# 4ch_mosfet_switch.net
KiCad netlist of a schematic drawn in EAGLE
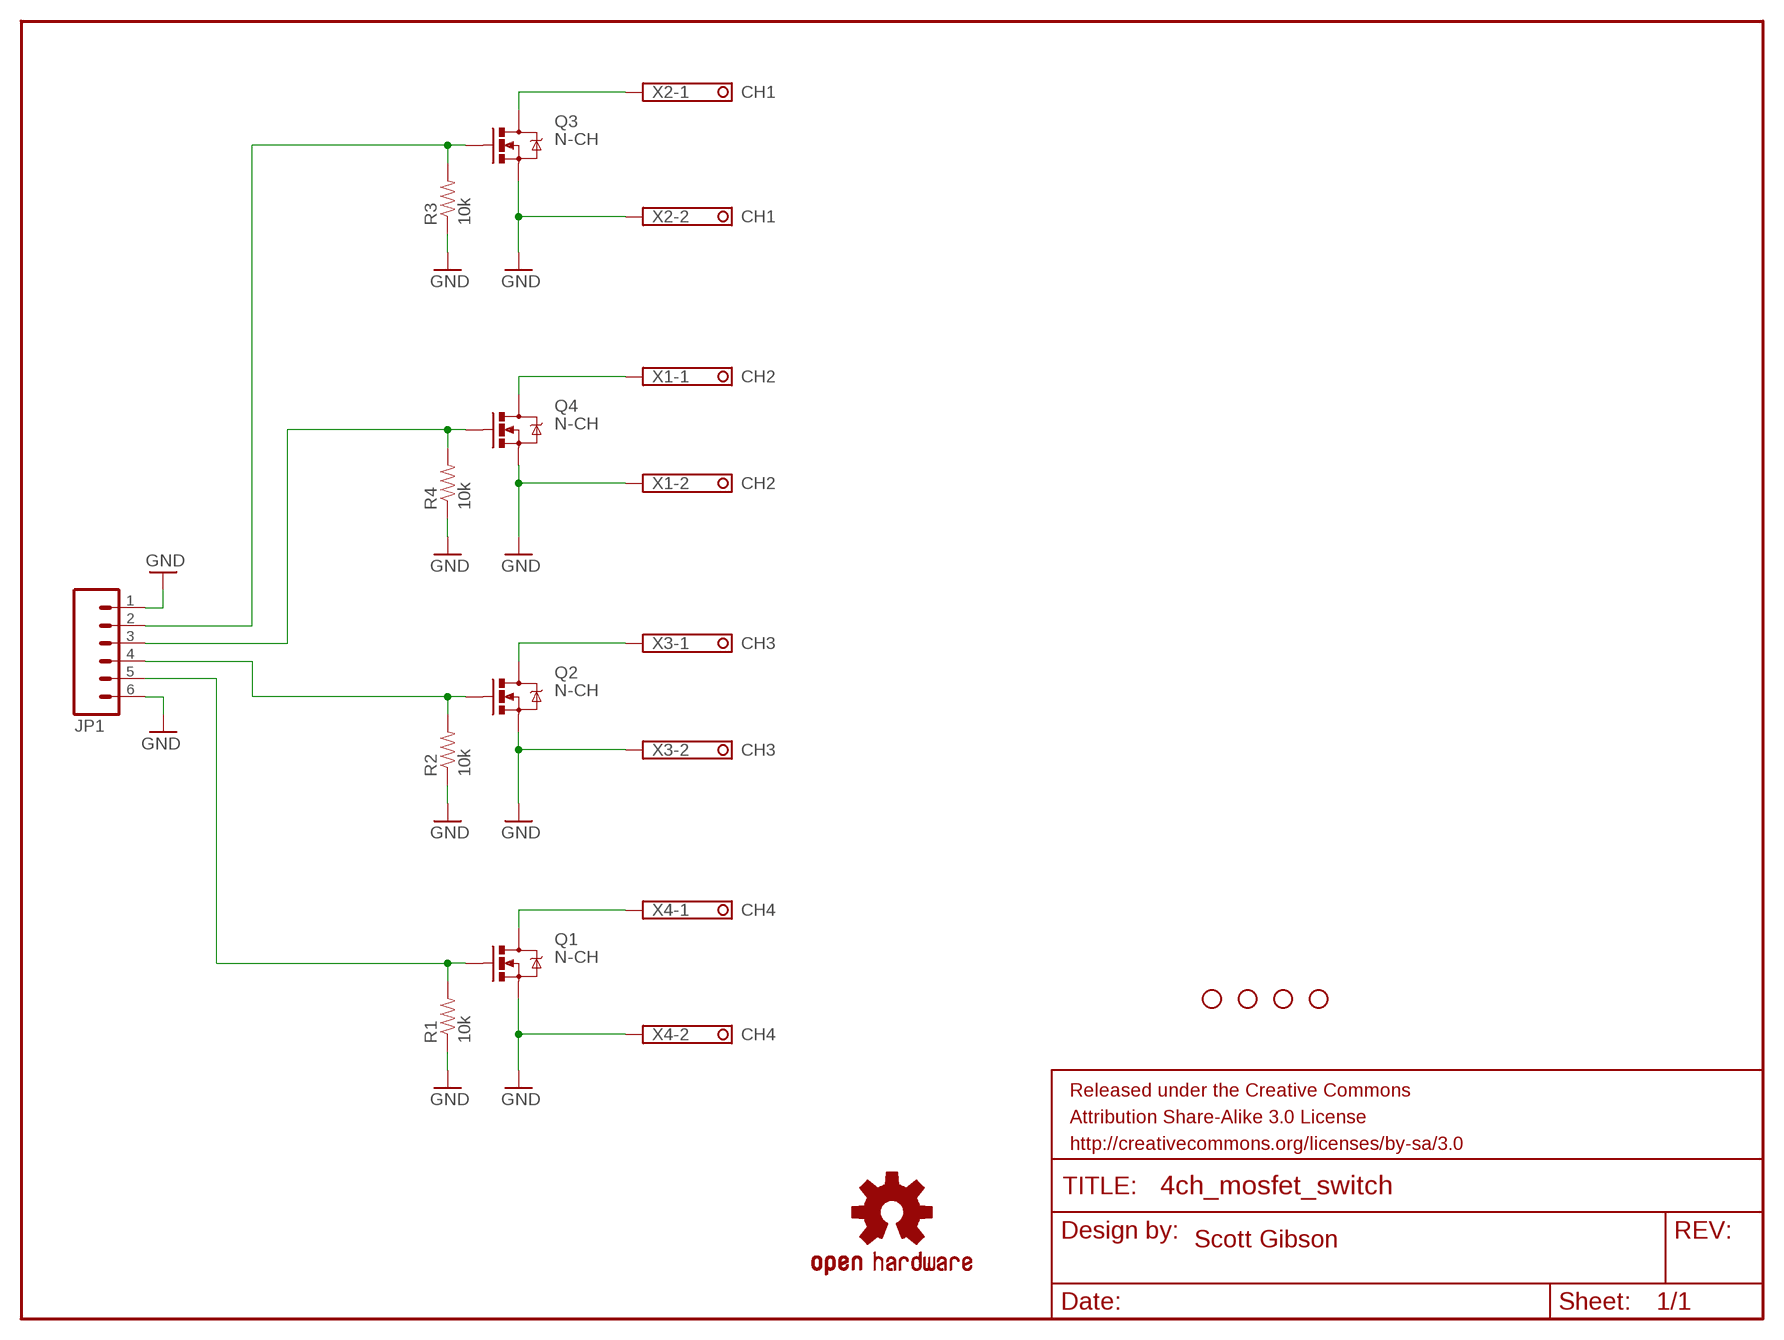
[diagram p0: schematic, sheet 1]

(export (version "E")
  (design (tool "Eeschema 10.0.6"))
  (components
    (comp (ref "FRAME1")
      (value "FRAME-LETTER")
      (footprint "eagle-import:CREATIVE_COMMONS")
      (libsource (lib "eagle-import") (part "FRAME-LETTER"))
    )
    (comp (ref "JP1")
      (value "M06LOCK_LONGPADS")
      (footprint "eagle-import:1X06_LOCK_LONGPADS")
      (libsource (lib "eagle-import") (part "M06LOCK_LONGPADS"))
    )
    (comp (ref "LOGO1")
      (value "OSHW-LOGOM")
      (footprint "eagle-import:OSHW-LOGO-M")
      (libsource (lib "eagle-import") (part "OSHW-LOGOM"))
    )
    (comp (ref "Q1")
      (value "N-CH")
      (footprint "eagle-import:TO220V")
      (libsource (lib "eagle-import") (part "MOSFET-NCHANNELFQP30N06L"))
    )
    (comp (ref "Q2")
      (value "N-CH")
      (footprint "eagle-import:TO220V")
      (libsource (lib "eagle-import") (part "MOSFET-NCHANNELFQP30N06L"))
    )
    (comp (ref "Q3")
      (value "N-CH")
      (footprint "eagle-import:TO220V")
      (libsource (lib "eagle-import") (part "MOSFET-NCHANNELFQP30N06L"))
    )
    (comp (ref "Q4")
      (value "N-CH")
      (footprint "eagle-import:TO220V")
      (libsource (lib "eagle-import") (part "MOSFET-NCHANNELFQP30N06L"))
    )
    (comp (ref "R1")
      (value "10k")
      (footprint "eagle-import:AXIAL-0.3")
      (libsource (lib "eagle-import") (part "RESISTORAXIAL-0.3"))
    )
    (comp (ref "R2")
      (value "10k")
      (footprint "eagle-import:AXIAL-0.3")
      (libsource (lib "eagle-import") (part "RESISTORAXIAL-0.3"))
    )
    (comp (ref "R3")
      (value "10k")
      (footprint "eagle-import:AXIAL-0.3")
      (libsource (lib "eagle-import") (part "RESISTORAXIAL-0.3"))
    )
    (comp (ref "R4")
      (value "10k")
      (footprint "eagle-import:AXIAL-0.3")
      (libsource (lib "eagle-import") (part "RESISTORAXIAL-0.3"))
    )
    (comp (ref "STANDOFF1")
      (value "STAND-OFF")
      (footprint "eagle-import:STAND-OFF")
      (libsource (lib "eagle-import") (part "STAND-OFF"))
    )
    (comp (ref "STANDOFF2")
      (value "STAND-OFF")
      (footprint "eagle-import:STAND-OFF")
      (libsource (lib "eagle-import") (part "STAND-OFF"))
    )
    (comp (ref "STANDOFF3")
      (value "STAND-OFF")
      (footprint "eagle-import:STAND-OFF")
      (libsource (lib "eagle-import") (part "STAND-OFF"))
    )
    (comp (ref "STANDOFF4")
      (value "STAND-OFF")
      (footprint "eagle-import:STAND-OFF")
      (libsource (lib "eagle-import") (part "STAND-OFF"))
    )
    (comp (ref "X1")
      (value "CH2")
      (footprint "eagle-import:1751248")
      (libsource (lib "eagle-import") (part "1751248"))
    )
    (comp (ref "X2")
      (value "CH1")
      (footprint "eagle-import:1751248")
      (libsource (lib "eagle-import") (part "1751248"))
    )
    (comp (ref "X3")
      (value "CH3")
      (footprint "eagle-import:1751248")
      (libsource (lib "eagle-import") (part "1751248"))
    )
    (comp (ref "X4")
      (value "CH4")
      (footprint "eagle-import:1751248")
      (libsource (lib "eagle-import") (part "1751248"))
    )
  )
  (nets
    (net (code "1") (name "GND") (class "Default")
      (node (ref "JP1") (pin "1") (pinfunction "1_1") (pintype "passive"))
      (node (ref "JP1") (pin "6") (pinfunction "6_6") (pintype "passive"))
      (node (ref "Q1") (pin "3") (pinfunction "S_3") (pintype "passive"))
      (node (ref "Q2") (pin "3") (pinfunction "S_3") (pintype "passive"))
      (node (ref "Q3") (pin "3") (pinfunction "S_3") (pintype "passive"))
      (node (ref "Q4") (pin "3") (pinfunction "S_3") (pintype "passive"))
      (node (ref "R1") (pin "P$1") (pinfunction "1_P$1") (pintype "passive"))
      (node (ref "R2") (pin "P$1") (pinfunction "1_P$1") (pintype "passive"))
      (node (ref "R3") (pin "P$1") (pinfunction "1_P$1") (pintype "passive"))
      (node (ref "R4") (pin "P$1") (pinfunction "1_P$1") (pintype "passive"))
      (node (ref "X1") (pin "2") (pinfunction "K_2") (pintype "passive"))
      (node (ref "X2") (pin "2") (pinfunction "K_2") (pintype "passive"))
      (node (ref "X3") (pin "2") (pinfunction "K_2") (pintype "passive"))
      (node (ref "X4") (pin "2") (pinfunction "K_2") (pintype "passive"))
    )
    (net (code "2") (name "Net-(Q1-D)") (class "Default")
      (node (ref "Q1") (pin "2") (pinfunction "D_2") (pintype "passive"))
      (node (ref "X4") (pin "1") (pinfunction "K_1") (pintype "passive"))
    )
    (net (code "3") (name "Net-(Q1-G)") (class "Default")
      (node (ref "JP1") (pin "5") (pinfunction "5_5") (pintype "passive"))
      (node (ref "Q1") (pin "1") (pinfunction "G_1") (pintype "passive"))
      (node (ref "R1") (pin "P$2") (pinfunction "2_P$2") (pintype "passive"))
    )
    (net (code "4") (name "Net-(Q2-D)") (class "Default")
      (node (ref "Q2") (pin "2") (pinfunction "D_2") (pintype "passive"))
      (node (ref "X3") (pin "1") (pinfunction "K_1") (pintype "passive"))
    )
    (net (code "5") (name "Net-(Q2-G)") (class "Default")
      (node (ref "JP1") (pin "4") (pinfunction "4_4") (pintype "passive"))
      (node (ref "Q2") (pin "1") (pinfunction "G_1") (pintype "passive"))
      (node (ref "R2") (pin "P$2") (pinfunction "2_P$2") (pintype "passive"))
    )
    (net (code "6") (name "Net-(Q3-D)") (class "Default")
      (node (ref "Q3") (pin "2") (pinfunction "D_2") (pintype "passive"))
      (node (ref "X2") (pin "1") (pinfunction "K_1") (pintype "passive"))
    )
    (net (code "7") (name "Net-(Q3-G)") (class "Default")
      (node (ref "JP1") (pin "2") (pinfunction "2_2") (pintype "passive"))
      (node (ref "Q3") (pin "1") (pinfunction "G_1") (pintype "passive"))
      (node (ref "R3") (pin "P$2") (pinfunction "2_P$2") (pintype "passive"))
    )
    (net (code "8") (name "Net-(Q4-D)") (class "Default")
      (node (ref "Q4") (pin "2") (pinfunction "D_2") (pintype "passive"))
      (node (ref "X1") (pin "1") (pinfunction "K_1") (pintype "passive"))
    )
    (net (code "9") (name "Net-(Q4-G)") (class "Default")
      (node (ref "JP1") (pin "3") (pinfunction "3_3") (pintype "passive"))
      (node (ref "Q4") (pin "1") (pinfunction "G_1") (pintype "passive"))
      (node (ref "R4") (pin "P$2") (pinfunction "2_P$2") (pintype "passive"))
    )
  )
)
